# RGMII_ETH_PHY.net
KiCad netlist of a schematic drawn in Altium Designer
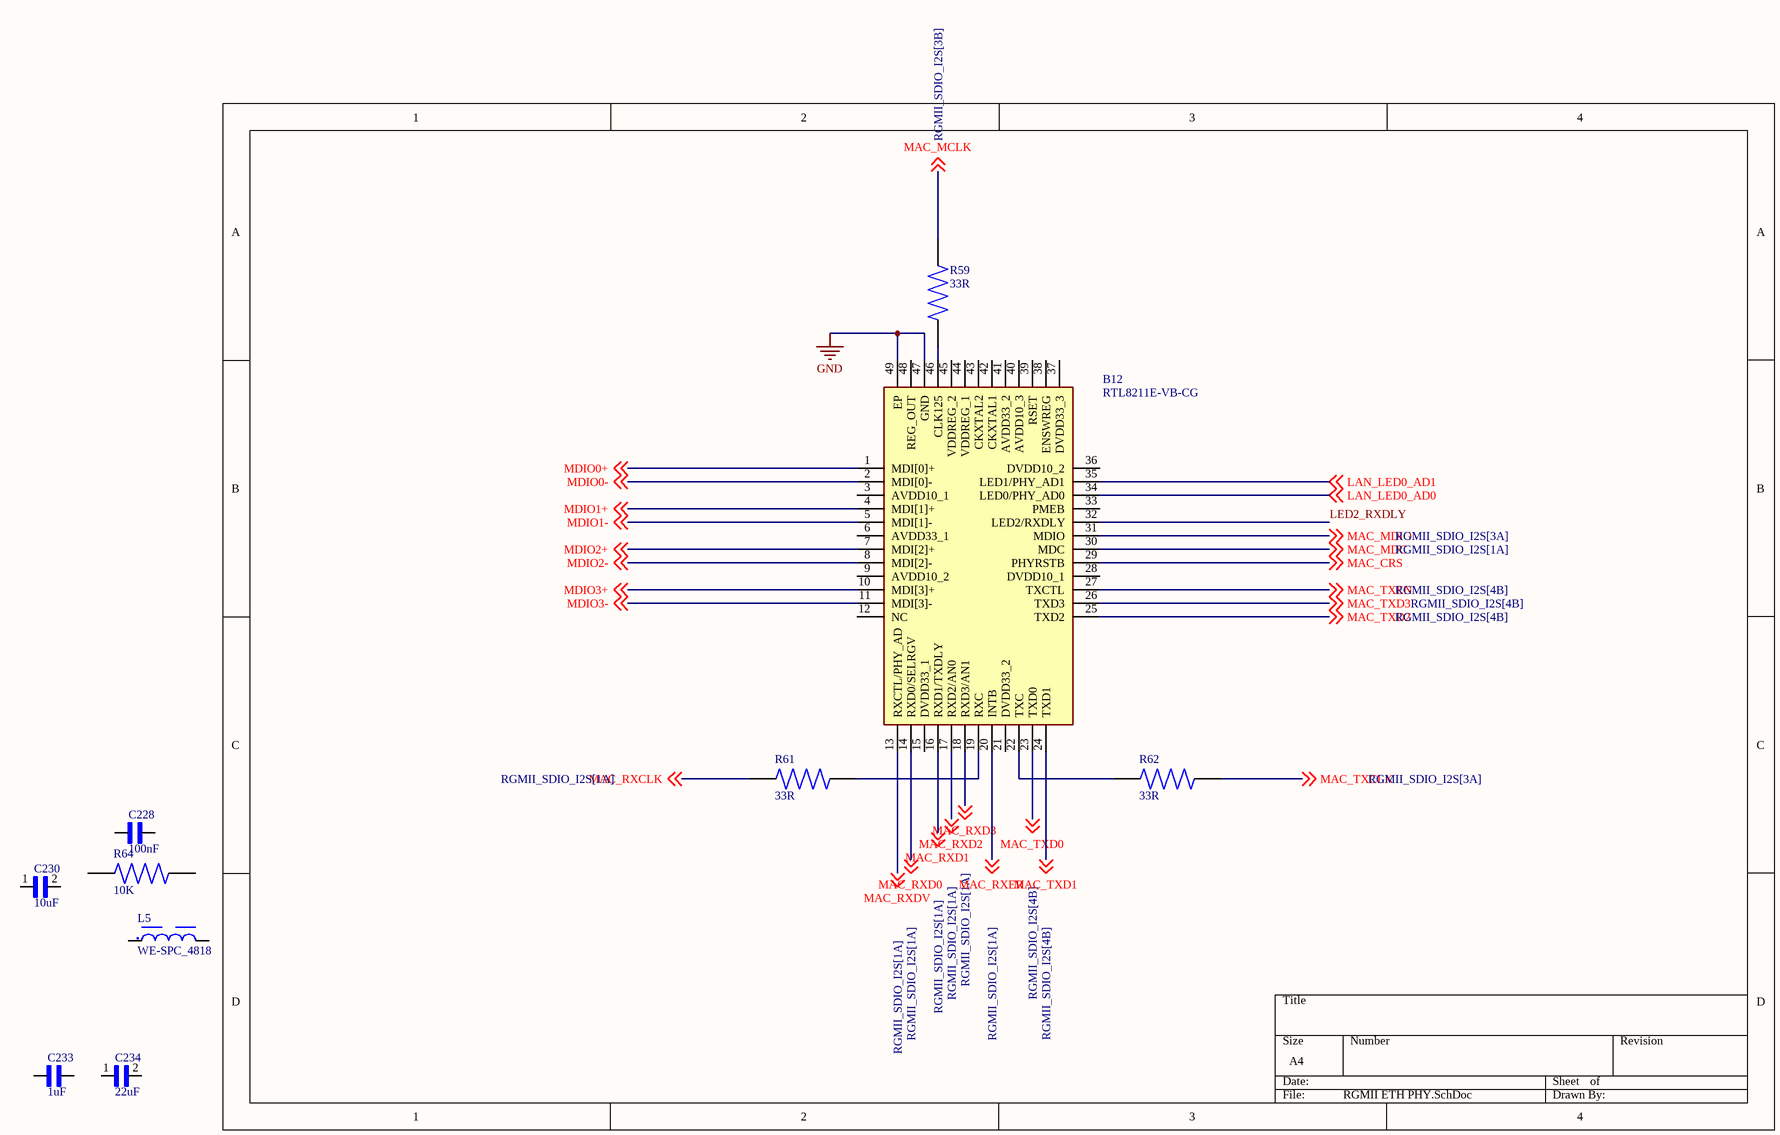
[diagram p0: RGMII ETH PHY.SchDoc]

(export (version "E")
  (design (tool "Eeschema 10.0.6"))
  (components
    (comp (ref "B12")
      (value "RTL8211E-VB-CG")
      (footprint "QFN40P600X600X100-49N")
      (description "h")
      (libsource (lib "RTL8211E-VB-CG") (part "RTL8211E-VB-CG"))
    )
    (comp (ref "C228")
      (value "100nF")
      (footprint "CAPC2012X90N")
      (description "Capacitor: ceramic; MLCC; 100nF; 25V; X7R; Â±10%; SMD; 0805")
      (fields (field (name "MF") "Vishay Vitramon") (field (name "MP") "VJ0805Y104KXXCW1BC"))
      (libsource (lib "VJ0805Y104KXXCW1BC") (part "VJ0805Y104KXXCW1BC"))
    )
    (comp (ref "C230")
      (value "10uF")
      (footprint "CAPC5035X300N")
      (description "10ÂµF Â±20% 16V Ceramic Capacitor X7R Nonstandard SMD")
      (fields (field (name "MF") "TDK") (field (name "MP") "CKG45KX7R1C106M290JH"))
      (libsource (lib "CKG45KX7R1C106M290JH") (part "CKG45KX7R1C106M290JH"))
    )
    (comp (ref "C233")
      (value "1uF")
      (footprint "CAPC3225X140N")
      (description "Capacitor;Ceramic;Cap;1.00uF;Tol+10%;SMT;Vol-Rtg 50V;High Cap.;X7R;TR ¦ KEMET C1210C105K5RACTU")
      (fields (field (name "MF") "KEMET") (field (name "MP") "C1210C105K5RACTU"))
      (libsource (lib "C1210C105K5RACTU") (part "C1210C105K5RACTU"))
    )
    (comp (ref "C234")
      (value "22uF")
      (footprint "CAPC6050X550N")
      (description "22ÂµF Â±20% 50V Ceramic Capacitor X7S Stacked SMD, 2 J-Lead")
      (fields (field (name "MP") "CKG57NX7S1H226M500JJ"))
      (libsource (lib "CKG57NX7S1H226M500JJ") (part "CKG57NX7S1H226M500JJ"))
    )
    (comp (ref "L5")
      (value "WE-SPC_4818")
      (footprint "WE-SPC_4818")
      (description "10 ÂµH Shielded Drum Core, Wirewound Inductor 900 mA 248mOhm Max 1919 (4848 Metric)")
      (fields (field (name "MF") "WÃ¼rth Elektronik") (field (name "MP") "74408941100"))
      (libsource (lib "WE-SPC_4818") (part "WE-SPC_4818"))
    )
    (comp (ref "R59")
      (value "33R")
      (footprint "RES_ERA6AHD330V")
      (fields (field (name "MP") "ERA6AHD330V"))
      (libsource (lib "ERA6AHD330V") (part "ERA6AHD330V"))
    )
    (comp (ref "R61")
      (value "33R")
      (footprint "RES_ERA6AHD330V")
      (fields (field (name "MP") "ERA6AHD330V"))
      (libsource (lib "ERA6AHD330V") (part "ERA6AHD330V"))
    )
    (comp (ref "R62")
      (value "33R")
      (footprint "RES_ERA6AHD330V")
      (fields (field (name "MP") "ERA6AHD330V"))
      (libsource (lib "ERA6AHD330V") (part "ERA6AHD330V"))
    )
    (comp (ref "R64")
      (value "10K")
      (footprint "RES_ERA3ARB103V")
      (fields (field (name "MP") "ERA3ARB103V"))
      (libsource (lib "ERA3ARB103V") (part "ERA3ARB103V"))
    )
  )
  (nets
    (net (code "1") (name "/LED2_RXDLY") (class "Default")
      (node (ref "B12") (pin "32") (pinfunction "LED2/RXDLY_32") (pintype "passive"))
    )
    (net (code "2") (name "GND") (class "Default")
      (node (ref "B12") (pin "47") (pinfunction "GND_47") (pintype "passive"))
      (node (ref "B12") (pin "49") (pinfunction "EP_49") (pintype "passive"))
    )
    (net (code "3") (name "LAN_LED0_AD0") (class "Default")
      (node (ref "B12") (pin "34") (pinfunction "LED0/PHY_AD0_34") (pintype "passive"))
    )
    (net (code "4") (name "LAN_LED0_AD1") (class "Default")
      (node (ref "B12") (pin "35") (pinfunction "LED1/PHY_AD1_35") (pintype "passive"))
    )
    (net (code "5") (name "MAC_CRS") (class "Default")
      (node (ref "B12") (pin "29") (pinfunction "PHYRSTB_29") (pintype "passive"))
    )
    (net (code "6") (name "MAC_MCLK") (class "Default")
      (node (ref "R59") (pin "1") (pinfunction "1_1") (pintype "passive"))
    )
    (net (code "7") (name "MAC_MDC") (class "Default")
      (node (ref "B12") (pin "30") (pinfunction "MDC_30") (pintype "passive"))
    )
    (net (code "8") (name "MAC_MDIO") (class "Default")
      (node (ref "B12") (pin "31") (pinfunction "MDIO_31") (pintype "passive"))
    )
    (net (code "9") (name "MAC_RXCLK") (class "Default")
      (node (ref "R61") (pin "2") (pinfunction "2_2") (pintype "passive"))
    )
    (net (code "10") (name "MAC_RXD0") (class "Default")
      (node (ref "B12") (pin "14") (pinfunction "RXD0/SELRGV_14") (pintype "passive"))
    )
    (net (code "11") (name "MAC_RXD1") (class "Default")
      (node (ref "B12") (pin "16") (pinfunction "RXD1/TXDLY_16") (pintype "passive"))
    )
    (net (code "12") (name "MAC_RXD2") (class "Default")
      (node (ref "B12") (pin "17") (pinfunction "RXD2/AN0_17") (pintype "passive"))
    )
    (net (code "13") (name "MAC_RXD3") (class "Default")
      (node (ref "B12") (pin "18") (pinfunction "RXD3/AN1_18") (pintype "passive"))
    )
    (net (code "14") (name "MAC_RXDV") (class "Default")
      (node (ref "B12") (pin "13") (pinfunction "RXCTL/PHY_AD_13") (pintype "passive"))
    )
    (net (code "15") (name "MAC_RXER") (class "Default")
      (node (ref "B12") (pin "20") (pinfunction "INTB_20") (pintype "passive"))
    )
    (net (code "16") (name "MAC_TXCLK") (class "Default")
      (node (ref "R62") (pin "1") (pinfunction "1_1") (pintype "passive"))
    )
    (net (code "17") (name "MAC_TXD0") (class "Default")
      (node (ref "B12") (pin "23") (pinfunction "TXD0_23") (pintype "passive"))
    )
    (net (code "18") (name "MAC_TXD1") (class "Default")
      (node (ref "B12") (pin "24") (pinfunction "TXD1_24") (pintype "passive"))
    )
    (net (code "19") (name "MAC_TXD2") (class "Default")
      (node (ref "B12") (pin "25") (pinfunction "TXD2_25") (pintype "passive"))
    )
    (net (code "20") (name "MAC_TXD3") (class "Default")
      (node (ref "B12") (pin "26") (pinfunction "TXD3_26") (pintype "passive"))
    )
    (net (code "21") (name "MAC_TXEN") (class "Default")
      (node (ref "B12") (pin "27") (pinfunction "TXCTL_27") (pintype "passive"))
    )
    (net (code "22") (name "MDIO0+") (class "Default")
      (node (ref "B12") (pin "1") (pinfunction "MDI[0]+_1") (pintype "passive"))
    )
    (net (code "23") (name "MDIO0-") (class "Default")
      (node (ref "B12") (pin "2") (pinfunction "MDI[0]-_2") (pintype "passive"))
    )
    (net (code "24") (name "MDIO1+") (class "Default")
      (node (ref "B12") (pin "4") (pinfunction "MDI[1]+_4") (pintype "passive"))
    )
    (net (code "25") (name "MDIO1-") (class "Default")
      (node (ref "B12") (pin "5") (pinfunction "MDI[1]-_5") (pintype "passive"))
    )
    (net (code "26") (name "MDIO2+") (class "Default")
      (node (ref "B12") (pin "7") (pinfunction "MDI[2]+_7") (pintype "passive"))
    )
    (net (code "27") (name "MDIO2-") (class "Default")
      (node (ref "B12") (pin "8") (pinfunction "MDI[2]-_8") (pintype "passive"))
    )
    (net (code "28") (name "MDIO3+") (class "Default")
      (node (ref "B12") (pin "10") (pinfunction "MDI[3]+_10") (pintype "passive"))
    )
    (net (code "29") (name "MDIO3-") (class "Default")
      (node (ref "B12") (pin "11") (pinfunction "MDI[3]-_11") (pintype "passive"))
    )
    (net (code "30") (name "Net-(B12-CLK125)") (class "Default")
      (node (ref "B12") (pin "46") (pinfunction "CLK125_46") (pintype "passive"))
      (node (ref "R59") (pin "2") (pinfunction "2_2") (pintype "passive"))
    )
    (net (code "31") (name "Net-(B12-RXC)") (class "Default")
      (node (ref "B12") (pin "19") (pinfunction "RXC_19") (pintype "passive"))
      (node (ref "R61") (pin "1") (pinfunction "1_1") (pintype "passive"))
    )
    (net (code "32") (name "Net-(B12-TXC)") (class "Default")
      (node (ref "B12") (pin "22") (pinfunction "TXC_22") (pintype "passive"))
      (node (ref "R62") (pin "2") (pinfunction "2_2") (pintype "passive"))
    )
    (net (code "33") (name "unconnected-(B12-AVDD10_1-Pad3)") (class "Default")
      (node (ref "B12") (pin "3") (pinfunction "AVDD10_1_3") (pintype "passive"))
    )
    (net (code "34") (name "unconnected-(B12-AVDD10_2-Pad9)") (class "Default")
      (node (ref "B12") (pin "9") (pinfunction "AVDD10_2_9") (pintype "passive"))
    )
    (net (code "35") (name "unconnected-(B12-AVDD10_3-Pad40)") (class "Default")
      (node (ref "B12") (pin "40") (pinfunction "AVDD10_3_40") (pintype "passive"))
    )
    (net (code "36") (name "unconnected-(B12-AVDD33_1-Pad6)") (class "Default")
      (node (ref "B12") (pin "6") (pinfunction "AVDD33_1_6") (pintype "passive"))
    )
    (net (code "37") (name "unconnected-(B12-AVDD33_2-Pad41)") (class "Default")
      (node (ref "B12") (pin "41") (pinfunction "AVDD33_2_41") (pintype "passive"))
    )
    (net (code "38") (name "unconnected-(B12-CKXTAL1-Pad42)") (class "Default")
      (node (ref "B12") (pin "42") (pinfunction "CKXTAL1_42") (pintype "passive"))
    )
    (net (code "39") (name "unconnected-(B12-CKXTAL2-Pad43)") (class "Default")
      (node (ref "B12") (pin "43") (pinfunction "CKXTAL2_43") (pintype "passive"))
    )
    (net (code "40") (name "unconnected-(B12-DVDD10_1-Pad28)") (class "Default")
      (node (ref "B12") (pin "28") (pinfunction "DVDD10_1_28") (pintype "passive"))
    )
    (net (code "41") (name "unconnected-(B12-DVDD10_2-Pad36)") (class "Default")
      (node (ref "B12") (pin "36") (pinfunction "DVDD10_2_36") (pintype "passive"))
    )
    (net (code "42") (name "unconnected-(B12-DVDD33_1-Pad15)") (class "Default")
      (node (ref "B12") (pin "15") (pinfunction "DVDD33_1_15") (pintype "passive"))
    )
    (net (code "43") (name "unconnected-(B12-DVDD33_2-Pad21)") (class "Default")
      (node (ref "B12") (pin "21") (pinfunction "DVDD33_2_21") (pintype "passive"))
    )
    (net (code "44") (name "unconnected-(B12-DVDD33_3-Pad37)") (class "Default")
      (node (ref "B12") (pin "37") (pinfunction "DVDD33_3_37") (pintype "passive"))
    )
    (net (code "45") (name "unconnected-(B12-ENSWREG-Pad38)") (class "Default")
      (node (ref "B12") (pin "38") (pinfunction "ENSWREG_38") (pintype "passive"))
    )
    (net (code "46") (name "unconnected-(B12-NC-Pad12)") (class "Default")
      (node (ref "B12") (pin "12") (pinfunction "NC_12") (pintype "passive"))
    )
    (net (code "47") (name "unconnected-(B12-PMEB-Pad33)") (class "Default")
      (node (ref "B12") (pin "33") (pinfunction "PMEB_33") (pintype "passive"))
    )
    (net (code "48") (name "unconnected-(B12-REG_OUT-Pad48)") (class "Default")
      (node (ref "B12") (pin "48") (pinfunction "REG_OUT_48") (pintype "passive"))
    )
    (net (code "49") (name "unconnected-(B12-RSET-Pad39)") (class "Default")
      (node (ref "B12") (pin "39") (pinfunction "RSET_39") (pintype "passive"))
    )
    (net (code "50") (name "unconnected-(B12-VDDREG_1-Pad44)") (class "Default")
      (node (ref "B12") (pin "44") (pinfunction "VDDREG_1_44") (pintype "passive"))
    )
    (net (code "51") (name "unconnected-(B12-VDDREG_2-Pad45)") (class "Default")
      (node (ref "B12") (pin "45") (pinfunction "VDDREG_2_45") (pintype "passive"))
    )
    (net (code "52") (name "unconnected-(C228-Pad1)") (class "Default")
      (node (ref "C228") (pin "1") (pinfunction "1_1") (pintype "passive"))
    )
    (net (code "53") (name "unconnected-(C228-Pad2)") (class "Default")
      (node (ref "C228") (pin "2") (pinfunction "2_2") (pintype "passive"))
    )
    (net (code "54") (name "unconnected-(C230-Pad1)") (class "Default")
      (node (ref "C230") (pin "1") (pinfunction "1_1") (pintype "passive"))
    )
    (net (code "55") (name "unconnected-(C230-Pad2)") (class "Default")
      (node (ref "C230") (pin "2") (pinfunction "2_2") (pintype "passive"))
    )
    (net (code "56") (name "unconnected-(C233-Pad1)") (class "Default")
      (node (ref "C233") (pin "1") (pinfunction "1_1") (pintype "passive"))
    )
    (net (code "57") (name "unconnected-(C233-Pad2)") (class "Default")
      (node (ref "C233") (pin "2") (pinfunction "2_2") (pintype "passive"))
    )
    (net (code "58") (name "unconnected-(C234-Pad1)") (class "Default")
      (node (ref "C234") (pin "1") (pinfunction "1_1") (pintype "passive"))
    )
    (net (code "59") (name "unconnected-(C234-Pad2)") (class "Default")
      (node (ref "C234") (pin "2") (pinfunction "2_2") (pintype "passive"))
    )
    (net (code "60") (name "unconnected-(L5-Pad1)") (class "Default")
      (node (ref "L5") (pin "1") (pinfunction "1_1") (pintype "passive"))
    )
    (net (code "61") (name "unconnected-(L5-Pad2)") (class "Default")
      (node (ref "L5") (pin "2") (pinfunction "2_2") (pintype "passive"))
    )
    (net (code "62") (name "unconnected-(R64-Pad1)") (class "Default")
      (node (ref "R64") (pin "1") (pinfunction "1_1") (pintype "passive"))
    )
    (net (code "63") (name "unconnected-(R64-Pad2)") (class "Default")
      (node (ref "R64") (pin "2") (pinfunction "2_2") (pintype "passive"))
    )
  )
)
